# toch_cap.net
KiCad netlist of a schematic drawn in Altium Designer
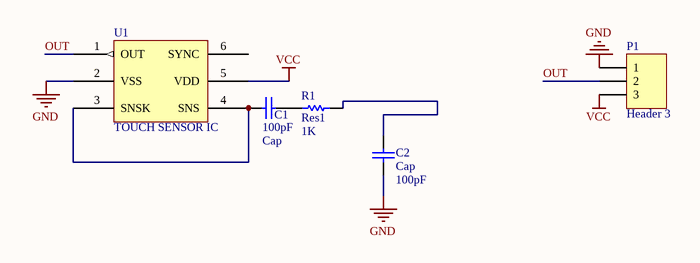
[diagram p0: toch_cap.SchDoc]

(export (version "E")
  (design (tool "Eeschema 10.0.6"))
  (components
    (comp (ref "C1")
      (value "Cap")
      (footprint "0805E")
      (description "Capacitor")
      (fields (field (name "ALTIUM_VALUE") "100pF") (field (name "PUBLISHER") "Altium Limited"))
      (libsource (lib "Miscellaneous Devices") (part "Cap"))
    )
    (comp (ref "C2")
      (value "Cap")
      (footprint "0805E")
      (description "Capacitor")
      (fields (field (name "ALTIUM_VALUE") "100pF") (field (name "PUBLISHER") "Altium Limited"))
      (libsource (lib "Miscellaneous Devices") (part "Cap"))
    )
    (comp (ref "P1")
      (value "Header 3")
      (footprint "HDR1X3")
      (description "Header, 3-Pin")
      (fields (field (name "PUBLISHER") "Altium Limited"))
      (libsource (lib "Miscellaneous Connectors") (part "Header 3"))
    )
    (comp (ref "R1")
      (value "Res1")
      (footprint "0805E")
      (description "Resistor")
      (fields (field (name "ALTIUM_VALUE") "1K") (field (name "PUBLISHER") "Altium Limited"))
      (libsource (lib "Miscellaneous Devices") (part "Res1"))
    )
    (comp (ref "U1")
      (value "TOUCH SENSOR IC")
      (footprint "SOT23-6_L")
      (libsource (lib "AT42QT1011") (part "AT42QT1011"))
    )
  )
  (nets
    (net (code "1") (name "/OUT") (class "Default")
      (node (ref "P1") (pin "2") (pinfunction "2_2") (pintype "passive"))
      (node (ref "U1") (pin "1") (pinfunction "OUT_1") (pintype "output"))
    )
    (net (code "2") (name "GND") (class "Default")
      (node (ref "C2") (pin "1") (pinfunction "1_1") (pintype "passive"))
      (node (ref "P1") (pin "1") (pinfunction "1_1") (pintype "passive"))
      (node (ref "U1") (pin "2") (pinfunction "VSS_2") (pintype "power_in"))
    )
    (net (code "3") (name "Net-(C1-Pad2)") (class "Default")
      (node (ref "C1") (pin "2") (pinfunction "2_2") (pintype "passive"))
      (node (ref "R1") (pin "1") (pinfunction "1_1") (pintype "passive"))
    )
    (net (code "4") (name "Net-(C2-Pad2)") (class "Default")
      (node (ref "C2") (pin "2") (pinfunction "2_2") (pintype "passive"))
      (node (ref "R1") (pin "2") (pinfunction "2_2") (pintype "passive"))
    )
    (net (code "5") (name "Net-(U1-SNS)") (class "Default")
      (node (ref "C1") (pin "1") (pinfunction "1_1") (pintype "passive"))
      (node (ref "U1") (pin "3") (pinfunction "SNSK_3") (pintype "passive"))
      (node (ref "U1") (pin "4") (pinfunction "SNS_4") (pintype "power_in"))
    )
    (net (code "6") (name "VCC") (class "Default")
      (node (ref "P1") (pin "3") (pinfunction "3_3") (pintype "passive"))
      (node (ref "U1") (pin "5") (pinfunction "VDD_5") (pintype "power_in"))
    )
    (net (code "7") (name "unconnected-(U1-SYNC-Pad6)") (class "Default")
      (node (ref "U1") (pin "6") (pinfunction "SYNC_6") (pintype "passive"))
    )
  )
)
